# opaq_n2.net
KiCad netlist of a schematic drawn in EAGLE
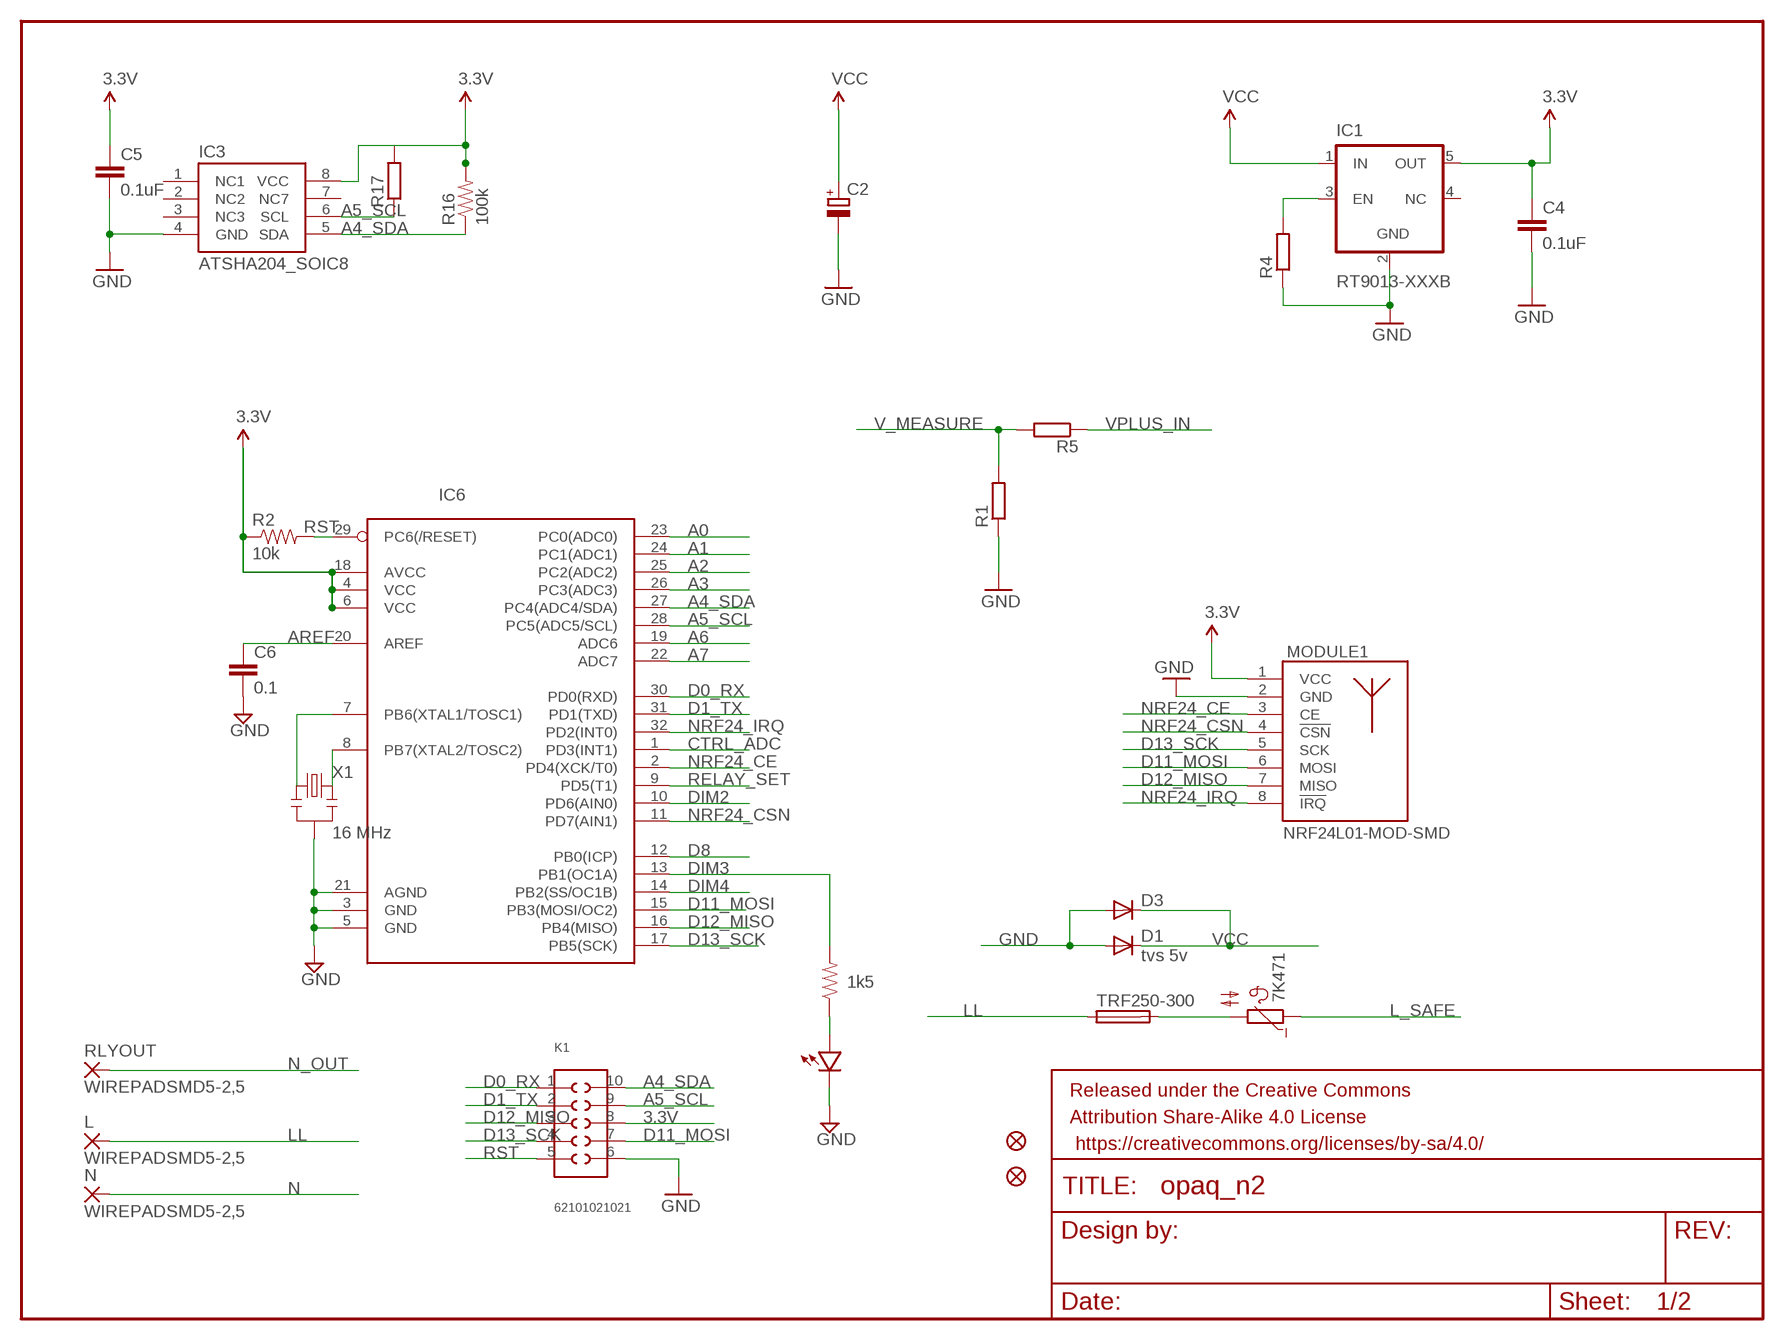
[diagram p0: schematic, sheet 1]
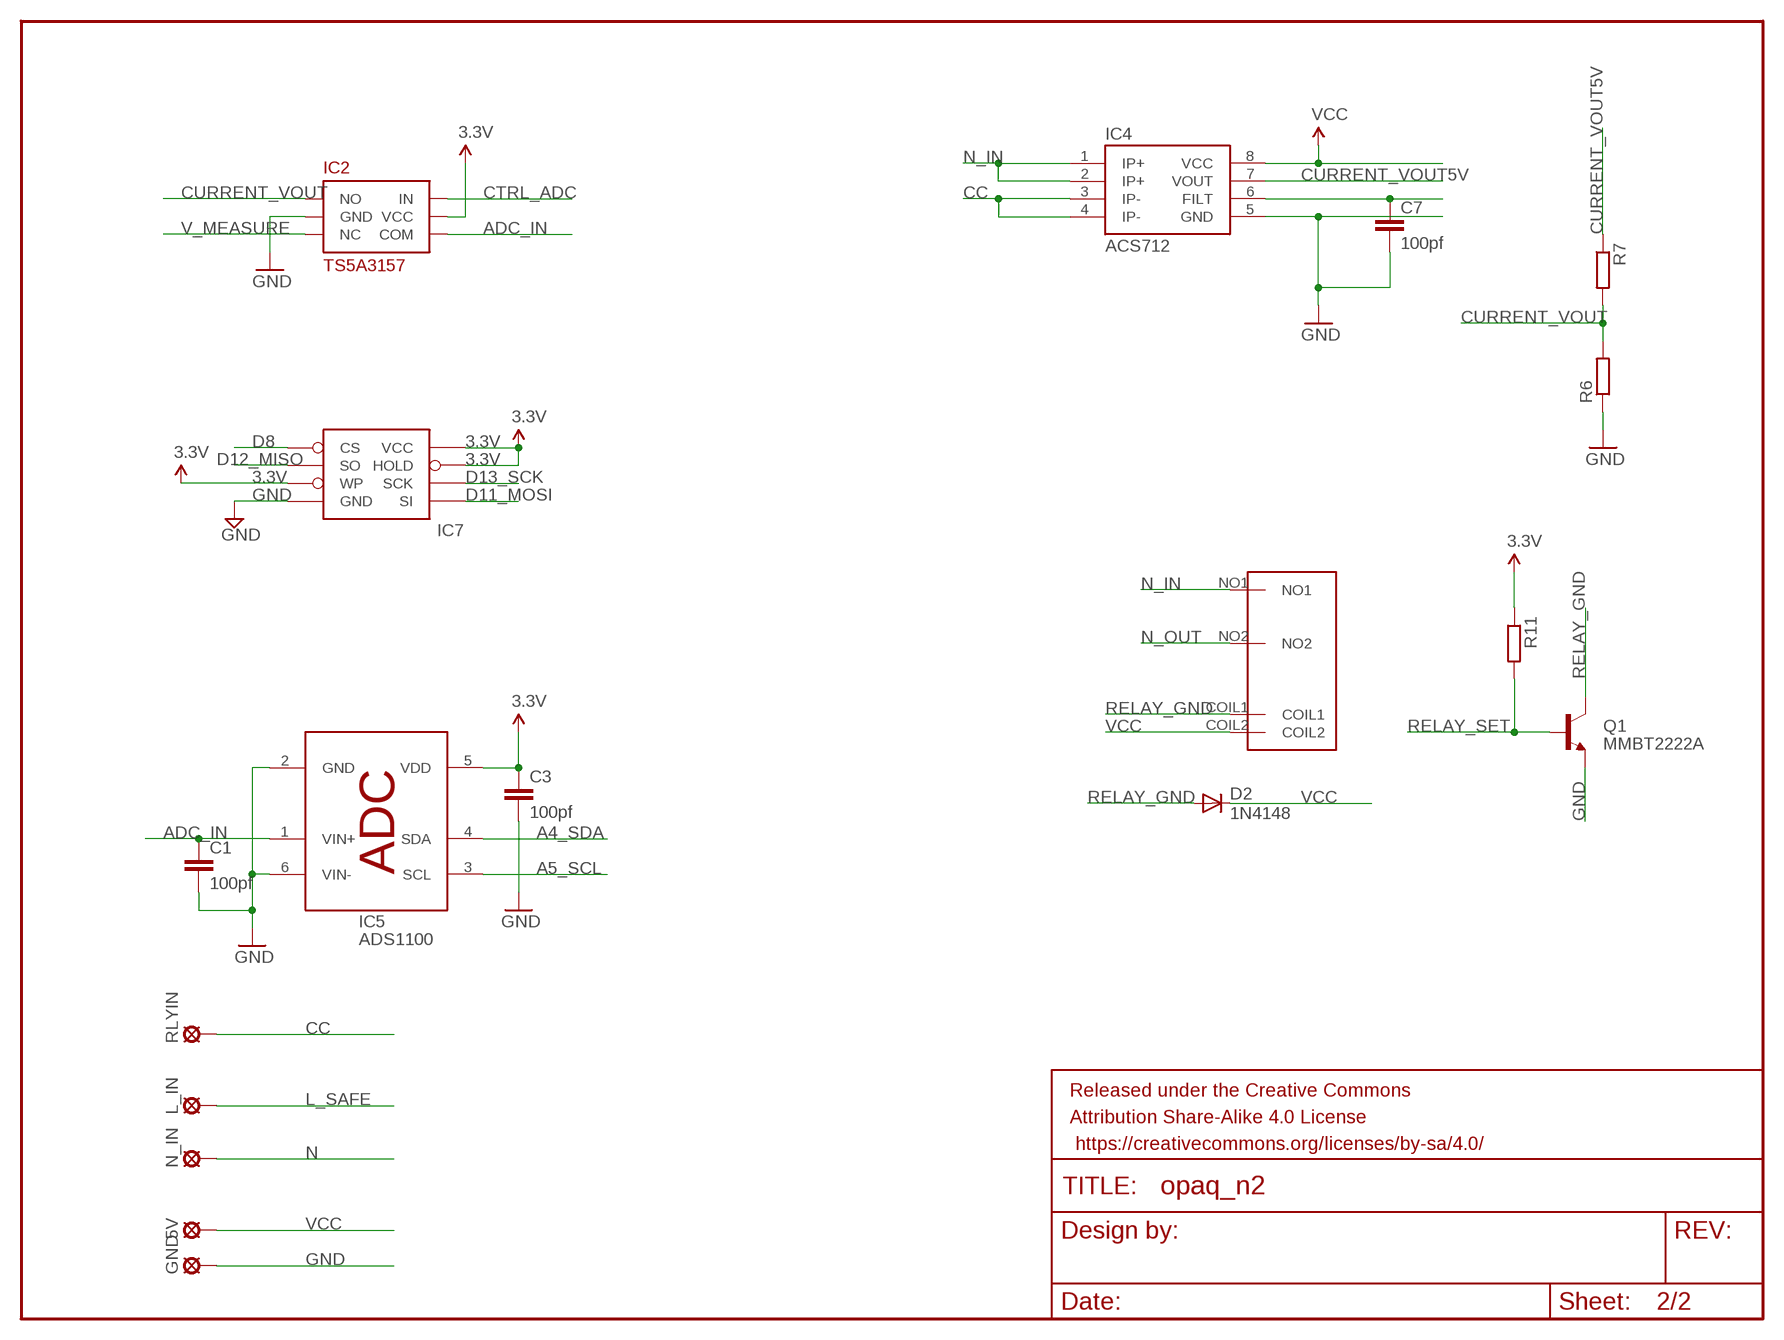
[diagram p1: schematic, sheet 2]

(export (version "E")
  (design (tool "Eeschema 10.0.6"))
  (components
    (comp (ref "7K471")
      (value "B57164")
      (footprint "eagle-import:B57164")
      (fields (field (name "MPN") "B57164K474K52"))
      (libsource (lib "eagle-import") (part "B57164"))
    )
    (comp (ref "C2")
      (value "CPOL-EUC/6032-28R")
      (footprint "eagle-import:C_6032-28R")
      (libsource (lib "eagle-import") (part "CPOL-EUC/6032-28R"))
    )
    (comp (ref "C4")
      (value "0.1uF")
      (footprint "eagle-import:0805")
      (libsource (lib "eagle-import") (part "SparkFun-Passives_CAP0805"))
    )
    (comp (ref "C5")
      (value "0.1uF")
      (footprint "eagle-import:0805")
      (libsource (lib "eagle-import") (part "SparkFun-Passives_CAP0805"))
    )
    (comp (ref "C6")
      (value "0.1")
      (footprint "eagle-import:0603-CAP")
      (libsource (lib "eagle-import") (part "CAP0603-CAP"))
    )
    (comp (ref "D1")
      (value "tvs 5v")
      (footprint "eagle-import:SOD-323")
      (libsource (lib "eagle-import") (part "DIODESOD"))
    )
    (comp (ref "D3")
      (value "DIODESMB")
      (footprint "eagle-import:SMB-DIODE")
      (libsource (lib "eagle-import") (part "DIODESMB"))
    )
    (comp (ref "DIM")
      (value "LED0603")
      (footprint "eagle-import:0603-LED")
      (libsource (lib "eagle-import") (part "LED0603"))
    )
    (comp (ref "FRAME1")
      (value "FRAME-LETTER")
      (footprint "eagle-import:CREATIVE_COMMONS")
      (libsource (lib "eagle-import") (part "FRAME-LETTER"))
    )
    (comp (ref "IC1")
      (value "RT9013-XXXB")
      (footprint "eagle-import:SOT23-5")
      (libsource (lib "eagle-import") (part "RT9013-XXXB"))
    )
    (comp (ref "IC3")
      (value "ATSHA204_SOIC8")
      (footprint "eagle-import:SOIC8")
      (libsource (lib "eagle-import") (part "ATSHA204_SOIC8"))
    )
    (comp (ref "IC6")
      (value "ATMega-328")
      (footprint "eagle-import:MLF32")
      (libsource (lib "eagle-import") (part "ATMEGA168/328MLF"))
    )
    (comp (ref "JP1")
      (value "FIDUCIAL1X2.5")
      (footprint "eagle-import:FIDUCIAL-1X2.5")
      (libsource (lib "eagle-import") (part "FIDUCIAL1X2.5"))
    )
    (comp (ref "JP2")
      (value "FIDUCIAL1X2.5")
      (footprint "eagle-import:FIDUCIAL-1X2.5")
      (libsource (lib "eagle-import") (part "FIDUCIAL1X2.5"))
    )
    (comp (ref "K1")
      (value "62101021021")
      (footprint "eagle-import:62101021021")
      (libsource (lib "eagle-import") (part "62101021021"))
    )
    (comp (ref "L")
      (value "WIREPADSMD5-2,5")
      (footprint "eagle-import:5-2,5")
      (libsource (lib "eagle-import") (part "WIREPADSMD5-2,5"))
    )
    (comp (ref "MODULE1")
      (value "NRF24L01-MOD-SMD")
      (footprint "eagle-import:SMD8-MODULE")
      (libsource (lib "eagle-import") (part "NRF24L01-MOD-SMD"))
    )
    (comp (ref "N")
      (value "WIREPADSMD5-2,5")
      (footprint "eagle-import:5-2,5")
      (libsource (lib "eagle-import") (part "WIREPADSMD5-2,5"))
    )
    (comp (ref "R1")
      (value "R-EU_R0805")
      (footprint "eagle-import:0805")
      (libsource (lib "eagle-import") (part "R-EU_R0805"))
    )
    (comp (ref "R2")
      (value "10k")
      (footprint "eagle-import:0603-RES")
      (libsource (lib "eagle-import") (part "RESISTOR0603-RES"))
    )
    (comp (ref "R3")
      (value "1k5")
      (footprint "eagle-import:0603-RES")
      (libsource (lib "eagle-import") (part "RESISTOR0603-RES"))
    )
    (comp (ref "R4")
      (value "R-EU_R0805")
      (footprint "eagle-import:0805")
      (libsource (lib "eagle-import") (part "R-EU_R0805"))
    )
    (comp (ref "R5")
      (value "R-EU_R0805")
      (footprint "eagle-import:0805")
      (libsource (lib "eagle-import") (part "R-EU_R0805"))
    )
    (comp (ref "R16")
      (value "100k")
      (footprint "eagle-import:0805")
      (libsource (lib "eagle-import") (part "SparkFun-Passives_RESISTOR0805-RES"))
    )
    (comp (ref "R17")
      (value "R-EU_R0805")
      (footprint "eagle-import:0805")
      (libsource (lib "eagle-import") (part "R-EU_R0805"))
    )
    (comp (ref "RLYOUT")
      (value "WIREPADSMD5-2,5")
      (footprint "eagle-import:5-2,5")
      (libsource (lib "eagle-import") (part "WIREPADSMD5-2,5"))
    )
    (comp (ref "TRF250-300")
      (value "TE5")
      (footprint "eagle-import:TE5")
      (libsource (lib "eagle-import") (part "TE5"))
    )
    (comp (ref "X1")
      (value "16 MHz")
      (footprint "eagle-import:RESONATOR-SMD")
      (libsource (lib "eagle-import") (part "RESONATORSMD"))
    )
    (comp (ref "5V")
      (value "MCS08")
      (footprint "eagle-import:MCS08")
      (libsource (lib "eagle-import") (part "MCS08"))
    )
    (comp (ref "C1")
      (value "100pf")
      (footprint "eagle-import:0402-CAP")
      (libsource (lib "eagle-import") (part "SparkFun-Passives_CAP0402-CAP"))
    )
    (comp (ref "C3")
      (value "100pf")
      (footprint "eagle-import:0402-CAP")
      (libsource (lib "eagle-import") (part "SparkFun-Passives_CAP0402-CAP"))
    )
    (comp (ref "C7")
      (value "100pf")
      (footprint "eagle-import:0402-CAP")
      (libsource (lib "eagle-import") (part "SparkFun-Passives_CAP0402-CAP"))
    )
    (comp (ref "D2")
      (value "1N4148")
      (footprint "eagle-import:SOD-323")
      (libsource (lib "eagle-import") (part "DIODESOD"))
    )
    (comp (ref "FRAME2")
      (value "FRAME-LETTERNO_PACKAGE")
      (footprint "eagle-import:DUMMY")
      (fields (field (name "DESIGNER") "Nobody"))
      (libsource (lib "eagle-import") (part "FRAME-LETTERNO_PACKAGE"))
    )
    (comp (ref "GND")
      (value "MCS08")
      (footprint "eagle-import:MCS08")
      (libsource (lib "eagle-import") (part "MCS08"))
    )
    (comp (ref "IC2")
      (value "TS5A3157")
      (footprint "eagle-import:SOT23-6")
      (libsource (lib "eagle-import") (part "TS5A3157"))
    )
    (comp (ref "IC4")
      (value "ACS712")
      (footprint "eagle-import:SO08")
      (libsource (lib "eagle-import") (part "ACS712"))
    )
    (comp (ref "IC5")
      (value "ADS1100")
      (footprint "eagle-import:SOT23-6")
      (fields (field (name "MF") "TI"))
      (libsource (lib "eagle-import") (part "ADS1100"))
    )
    (comp (ref "IC7")
      (value "AT25F512BWIDE_5.3MM")
      (footprint "eagle-import:SO08WIDE")
      (libsource (lib "eagle-import") (part "AT25F512BWIDE_5.3MM"))
    )
    (comp (ref "L_IN")
      (value "MCS08")
      (footprint "eagle-import:MCS08")
      (libsource (lib "eagle-import") (part "MCS08"))
    )
    (comp (ref "N_IN")
      (value "MCS08")
      (footprint "eagle-import:MCS08")
      (libsource (lib "eagle-import") (part "MCS08"))
    )
    (comp (ref "Q1")
      (value "MMBT2222A")
      (footprint "eagle-import:SOT23-3")
      (libsource (lib "eagle-import") (part "TRANSISTOR_NPNMMBT2222A"))
    )
    (comp (ref "R6")
      (value "R-EU_R0805")
      (footprint "eagle-import:0805")
      (libsource (lib "eagle-import") (part "R-EU_R0805"))
    )
    (comp (ref "R7")
      (value "R-EU_R0805")
      (footprint "eagle-import:0805")
      (libsource (lib "eagle-import") (part "R-EU_R0805"))
    )
    (comp (ref "R11")
      (value "R-EU_R0805")
      (footprint "eagle-import:0805")
      (libsource (lib "eagle-import") (part "R-EU_R0805"))
    )
    (comp (ref "RLYIN")
      (value "MCS08")
      (footprint "eagle-import:MCS08")
      (libsource (lib "eagle-import") (part "MCS08"))
    )
    (comp (ref "U$1")
      (value "OMRON_G6M-1A")
      (footprint "eagle-import:OMRON_G6M-1A")
      (libsource (lib "eagle-import") (part "OMRON_G6M-1A"))
    )
  )
  (nets
    (net (code "1") (name "3.3V") (class "Default")
      (node (ref "C3") (pin "1") (pinfunction "1_1") (pintype "passive"))
      (node (ref "C4") (pin "1") (pinfunction "1_1") (pintype "passive"))
      (node (ref "C5") (pin "1") (pinfunction "1_1") (pintype "passive"))
      (node (ref "IC1") (pin "5") (pinfunction "OUT_5") (pintype "passive"))
      (node (ref "IC2") (pin "5") (pinfunction "VCC_5") (pintype "bidirectional"))
      (node (ref "IC3") (pin "8") (pinfunction "VCC_8") (pintype "power_in"))
      (node (ref "IC5") (pin "5") (pinfunction "VDD_5") (pintype "power_in"))
      (node (ref "IC6") (pin "18") (pinfunction "AVCC_18") (pintype "bidirectional"))
      (node (ref "IC6") (pin "4") (pinfunction "VCC_4") (pintype "bidirectional"))
      (node (ref "IC6") (pin "6") (pinfunction "VCC_6") (pintype "bidirectional"))
      (node (ref "IC7") (pin "3") (pinfunction "WP_3") (pintype "bidirectional"))
      (node (ref "IC7") (pin "7") (pinfunction "HOLD_7") (pintype "bidirectional"))
      (node (ref "IC7") (pin "8") (pinfunction "VCC_8") (pintype "bidirectional"))
      (node (ref "K1") (pin "8") (pinfunction "8_8") (pintype "passive"))
      (node (ref "MODULE1") (pin "1") (pinfunction "VCC_1") (pintype "power_in"))
      (node (ref "R11") (pin "1") (pinfunction "1_1") (pintype "passive"))
      (node (ref "R16") (pin "2") (pinfunction "2_2") (pintype "passive"))
      (node (ref "R17") (pin "2") (pinfunction "2_2") (pintype "passive"))
      (node (ref "R2") (pin "1") (pinfunction "1_1") (pintype "passive"))
    )
    (net (code "2") (name "A0") (class "Default")
      (node (ref "IC6") (pin "23") (pinfunction "PC0(ADC0)_23") (pintype "bidirectional"))
    )
    (net (code "3") (name "A1") (class "Default")
      (node (ref "IC6") (pin "24") (pinfunction "PC1(ADC1)_24") (pintype "bidirectional"))
    )
    (net (code "4") (name "A2") (class "Default")
      (node (ref "IC6") (pin "25") (pinfunction "PC2(ADC2)_25") (pintype "bidirectional"))
    )
    (net (code "5") (name "A3") (class "Default")
      (node (ref "IC6") (pin "26") (pinfunction "PC3(ADC3)_26") (pintype "bidirectional"))
    )
    (net (code "6") (name "A4_SDA") (class "Default")
      (node (ref "IC3") (pin "5") (pinfunction "SDA_5") (pintype "bidirectional"))
      (node (ref "IC5") (pin "4") (pinfunction "SDA_4") (pintype "bidirectional"))
      (node (ref "IC6") (pin "27") (pinfunction "PC4(ADC4/SDA)_27") (pintype "bidirectional"))
      (node (ref "K1") (pin "10") (pinfunction "10_10") (pintype "passive"))
      (node (ref "R16") (pin "1") (pinfunction "1_1") (pintype "passive"))
    )
    (net (code "7") (name "A5_SCL") (class "Default")
      (node (ref "IC3") (pin "6") (pinfunction "SCL_6") (pintype "bidirectional"))
      (node (ref "IC5") (pin "3") (pinfunction "SCL_3") (pintype "input"))
      (node (ref "IC6") (pin "28") (pinfunction "PC5(ADC5/SCL)_28") (pintype "bidirectional"))
      (node (ref "K1") (pin "9") (pinfunction "9_9") (pintype "passive"))
      (node (ref "R17") (pin "1") (pinfunction "1_1") (pintype "passive"))
    )
    (net (code "8") (name "A6") (class "Default")
      (node (ref "IC6") (pin "19") (pinfunction "ADC6_19") (pintype "bidirectional"))
    )
    (net (code "9") (name "A7") (class "Default")
      (node (ref "IC6") (pin "22") (pinfunction "ADC7_22") (pintype "bidirectional"))
    )
    (net (code "10") (name "ADC_IN") (class "Default")
      (node (ref "C1") (pin "1") (pinfunction "1_1") (pintype "passive"))
      (node (ref "IC2") (pin "4") (pinfunction "COM_4") (pintype "bidirectional"))
      (node (ref "IC5") (pin "1") (pinfunction "VIN+_1") (pintype "input"))
    )
    (net (code "11") (name "AREF") (class "Default")
      (node (ref "C6") (pin "1") (pinfunction "1_1") (pintype "passive"))
      (node (ref "IC6") (pin "20") (pinfunction "AREF_20") (pintype "bidirectional"))
    )
    (net (code "12") (name "CC") (class "Default")
      (node (ref "IC4") (pin "3") (pinfunction "IP-_3") (pintype "bidirectional"))
      (node (ref "IC4") (pin "4") (pinfunction "IP-_4") (pintype "bidirectional"))
      (node (ref "RLYIN") (pin "MP") (pinfunction "MP_MP") (pintype "passive"))
    )
    (net (code "13") (name "CTRL_ADC") (class "Default")
      (node (ref "IC2") (pin "6") (pinfunction "IN_6") (pintype "bidirectional"))
      (node (ref "IC6") (pin "1") (pinfunction "PD3(INT1)_1") (pintype "bidirectional"))
    )
    (net (code "14") (name "CURRENT_VOUT") (class "Default")
      (node (ref "IC2") (pin "1") (pinfunction "NO_1") (pintype "bidirectional"))
      (node (ref "R6") (pin "2") (pinfunction "2_2") (pintype "passive"))
      (node (ref "R7") (pin "2") (pinfunction "2_2") (pintype "passive"))
    )
    (net (code "15") (name "CURRENT_VOUT5V") (class "Default")
      (node (ref "IC4") (pin "7") (pinfunction "VOUT_7") (pintype "bidirectional"))
      (node (ref "R7") (pin "1") (pinfunction "1_1") (pintype "passive"))
    )
    (net (code "16") (name "D0_RX") (class "Default")
      (node (ref "IC6") (pin "30") (pinfunction "PD0(RXD)_30") (pintype "bidirectional"))
      (node (ref "K1") (pin "1") (pinfunction "1_1") (pintype "passive"))
    )
    (net (code "17") (name "D1_TX") (class "Default")
      (node (ref "IC6") (pin "31") (pinfunction "PD1(TXD)_31") (pintype "bidirectional"))
      (node (ref "K1") (pin "2") (pinfunction "2_2") (pintype "passive"))
    )
    (net (code "18") (name "D8") (class "Default")
      (node (ref "IC6") (pin "12") (pinfunction "PB0(ICP)_12") (pintype "bidirectional"))
      (node (ref "IC7") (pin "1") (pinfunction "CS_1") (pintype "bidirectional"))
    )
    (net (code "19") (name "D11_MOSI") (class "Default")
      (node (ref "IC6") (pin "15") (pinfunction "PB3(MOSI/OC2)_15") (pintype "bidirectional"))
      (node (ref "IC7") (pin "5") (pinfunction "SI_5") (pintype "bidirectional"))
      (node (ref "K1") (pin "7") (pinfunction "7_7") (pintype "passive"))
      (node (ref "MODULE1") (pin "6") (pinfunction "MOSI_6") (pintype "input"))
    )
    (net (code "20") (name "D12_MISO") (class "Default")
      (node (ref "IC6") (pin "16") (pinfunction "PB4(MISO)_16") (pintype "bidirectional"))
      (node (ref "IC7") (pin "2") (pinfunction "SO_2") (pintype "bidirectional"))
      (node (ref "K1") (pin "3") (pinfunction "3_3") (pintype "passive"))
      (node (ref "MODULE1") (pin "7") (pinfunction "MISO_7") (pintype "output"))
    )
    (net (code "21") (name "D13_SCK") (class "Default")
      (node (ref "IC6") (pin "17") (pinfunction "PB5(SCK)_17") (pintype "bidirectional"))
      (node (ref "IC7") (pin "6") (pinfunction "SCK_6") (pintype "bidirectional"))
      (node (ref "K1") (pin "4") (pinfunction "4_4") (pintype "passive"))
      (node (ref "MODULE1") (pin "5") (pinfunction "SCK_5") (pintype "input"))
    )
    (net (code "22") (name "DIM2") (class "Default")
      (node (ref "IC6") (pin "10") (pinfunction "PD6(AIN0)_10") (pintype "bidirectional"))
    )
    (net (code "23") (name "DIM3") (class "Default")
      (node (ref "IC6") (pin "13") (pinfunction "PB1(OC1A)_13") (pintype "bidirectional"))
      (node (ref "R3") (pin "2") (pinfunction "2_2") (pintype "passive"))
    )
    (net (code "24") (name "DIM4") (class "Default")
      (node (ref "IC6") (pin "14") (pinfunction "PB2(SS/OC1B)_14") (pintype "bidirectional"))
    )
    (net (code "25") (name "GND") (class "Default")
      (node (ref "C1") (pin "2") (pinfunction "2_2") (pintype "passive"))
      (node (ref "C2") (pin "-") (pinfunction "-_-") (pintype "passive"))
      (node (ref "C3") (pin "2") (pinfunction "2_2") (pintype "passive"))
      (node (ref "C4") (pin "2") (pinfunction "2_2") (pintype "passive"))
      (node (ref "C5") (pin "2") (pinfunction "2_2") (pintype "passive"))
      (node (ref "C6") (pin "2") (pinfunction "2_2") (pintype "passive"))
      (node (ref "C7") (pin "2") (pinfunction "2_2") (pintype "passive"))
      (node (ref "D1") (pin "2") (pinfunction "A_2") (pintype "passive"))
      (node (ref "D3") (pin "A") (pinfunction "A_A") (pintype "passive"))
      (node (ref "DIM") (pin "MINUS") (pinfunction "MINUS_MINUS") (pintype "passive"))
      (node (ref "GND") (pin "MP") (pinfunction "MP_MP") (pintype "passive"))
      (node (ref "IC1") (pin "2") (pinfunction "GND_2") (pintype "power_in"))
      (node (ref "IC2") (pin "2") (pinfunction "GND_2") (pintype "bidirectional"))
      (node (ref "IC3") (pin "4") (pinfunction "GND_4") (pintype "power_in"))
      (node (ref "IC4") (pin "5") (pinfunction "GND_5") (pintype "bidirectional"))
      (node (ref "IC5") (pin "2") (pinfunction "GND_2") (pintype "power_in"))
      (node (ref "IC5") (pin "6") (pinfunction "VIN-_6") (pintype "input"))
      (node (ref "IC6") (pin "21") (pinfunction "AGND_21") (pintype "bidirectional"))
      (node (ref "IC6") (pin "3") (pinfunction "GND_3") (pintype "bidirectional"))
      (node (ref "IC6") (pin "5") (pinfunction "GND_5") (pintype "bidirectional"))
      (node (ref "IC7") (pin "4") (pinfunction "GND_4") (pintype "bidirectional"))
      (node (ref "K1") (pin "6") (pinfunction "6_6") (pintype "passive"))
      (node (ref "MODULE1") (pin "2") (pinfunction "GND_2") (pintype "power_in"))
      (node (ref "Q1") (pin "2") (pinfunction "E_2") (pintype "passive"))
      (node (ref "R1") (pin "1") (pinfunction "1_1") (pintype "passive"))
      (node (ref "R4") (pin "1") (pinfunction "1_1") (pintype "passive"))
      (node (ref "R6") (pin "1") (pinfunction "1_1") (pintype "passive"))
      (node (ref "X1") (pin "2") (pinfunction "2_2") (pintype "passive"))
    )
    (net (code "26") (name "LL") (class "Default")
      (node (ref "L") (pin "1") (pinfunction "P_1") (pintype "passive"))
      (node (ref "TRF250-300") (pin "1") (pinfunction "1_1") (pintype "passive"))
    )
    (net (code "27") (name "L_SAFE") (class "Default")
      (node (ref "7K471") (pin "1") (pinfunction "1_1") (pintype "passive"))
      (node (ref "L_IN") (pin "MP") (pinfunction "MP_MP") (pintype "passive"))
    )
    (net (code "28") (name "N") (class "Default")
      (node (ref "N") (pin "1") (pinfunction "P_1") (pintype "passive"))
      (node (ref "N_IN") (pin "MP") (pinfunction "MP_MP") (pintype "passive"))
    )
    (net (code "29") (name "NRF24_CE") (class "Default")
      (node (ref "IC6") (pin "2") (pinfunction "PD4(XCK/T0)_2") (pintype "bidirectional"))
      (node (ref "MODULE1") (pin "3") (pinfunction "CE_3") (pintype "input"))
    )
    (net (code "30") (name "NRF24_CSN") (class "Default")
      (node (ref "IC6") (pin "11") (pinfunction "PD7(AIN1)_11") (pintype "bidirectional"))
      (node (ref "MODULE1") (pin "4") (pinfunction "~{CSN}_4") (pintype "input"))
    )
    (net (code "31") (name "NRF24_IRQ") (class "Default")
      (node (ref "IC6") (pin "32") (pinfunction "PD2(INT0)_32") (pintype "bidirectional"))
      (node (ref "MODULE1") (pin "8") (pinfunction "~{IRQ}_8") (pintype "open_collector"))
    )
    (net (code "32") (name "N_IN") (class "Default")
      (node (ref "IC4") (pin "1") (pinfunction "IP+_1") (pintype "bidirectional"))
      (node (ref "IC4") (pin "2") (pinfunction "IP+_2") (pintype "bidirectional"))
      (node (ref "U$1") (pin "NO1") (pinfunction "NO1_NO1") (pintype "bidirectional"))
    )
    (net (code "33") (name "N_OUT") (class "Default")
      (node (ref "RLYOUT") (pin "1") (pinfunction "P_1") (pintype "passive"))
      (node (ref "U$1") (pin "NO2") (pinfunction "NO2_NO2") (pintype "bidirectional"))
    )
    (net (code "34") (name "Net-(7K471-Pad2)") (class "Default")
      (node (ref "7K471") (pin "2") (pinfunction "2_2") (pintype "passive"))
      (node (ref "TRF250-300") (pin "2") (pinfunction "2_2") (pintype "passive"))
    )
    (net (code "35") (name "Net-(DIM-PadPLUS)") (class "Default")
      (node (ref "DIM") (pin "PLUS") (pinfunction "PLUS_PLUS") (pintype "passive"))
      (node (ref "R3") (pin "1") (pinfunction "1_1") (pintype "passive"))
    )
    (net (code "36") (name "Net-(IC1-EN)") (class "Default")
      (node (ref "IC1") (pin "3") (pinfunction "EN_3") (pintype "input"))
      (node (ref "R4") (pin "2") (pinfunction "2_2") (pintype "passive"))
    )
    (net (code "37") (name "Net-(IC4-FILT)") (class "Default")
      (node (ref "C7") (pin "1") (pinfunction "1_1") (pintype "passive"))
      (node (ref "IC4") (pin "6") (pinfunction "FILT_6") (pintype "bidirectional"))
    )
    (net (code "38") (name "Net-(IC6-PB6(XTAL1{slash}TOSC1))") (class "Default")
      (node (ref "IC6") (pin "7") (pinfunction "PB6(XTAL1/TOSC1)_7") (pintype "bidirectional"))
      (node (ref "X1") (pin "1") (pinfunction "1_1") (pintype "passive"))
    )
    (net (code "39") (name "Net-(IC6-PB7(XTAL2{slash}TOSC2))") (class "Default")
      (node (ref "IC6") (pin "8") (pinfunction "PB7(XTAL2/TOSC2)_8") (pintype "bidirectional"))
      (node (ref "X1") (pin "3") (pinfunction "3_3") (pintype "passive"))
    )
    (net (code "40") (name "RELAY_GND") (class "Default")
      (node (ref "D2") (pin "2") (pinfunction "A_2") (pintype "passive"))
      (node (ref "Q1") (pin "3") (pinfunction "C_3") (pintype "passive"))
      (node (ref "U$1") (pin "COIL1") (pinfunction "COIL1_COIL1") (pintype "bidirectional"))
    )
    (net (code "41") (name "RELAY_SET") (class "Default")
      (node (ref "IC6") (pin "9") (pinfunction "PD5(T1)_9") (pintype "bidirectional"))
      (node (ref "Q1") (pin "1") (pinfunction "B_1") (pintype "passive"))
      (node (ref "R11") (pin "2") (pinfunction "2_2") (pintype "passive"))
    )
    (net (code "42") (name "RST") (class "Default")
      (node (ref "IC6") (pin "29") (pinfunction "PC6(/RESET)_29") (pintype "bidirectional"))
      (node (ref "K1") (pin "5") (pinfunction "5_5") (pintype "passive"))
      (node (ref "R2") (pin "2") (pinfunction "2_2") (pintype "passive"))
    )
    (net (code "43") (name "VCC") (class "Default")
      (node (ref "5V") (pin "MP") (pinfunction "MP_MP") (pintype "passive"))
      (node (ref "C2") (pin "+") (pinfunction "+_+") (pintype "passive"))
      (node (ref "D1") (pin "1") (pinfunction "C_1") (pintype "passive"))
      (node (ref "D2") (pin "1") (pinfunction "C_1") (pintype "passive"))
      (node (ref "D3") (pin "C") (pinfunction "C_C") (pintype "passive"))
      (node (ref "IC1") (pin "1") (pinfunction "IN_1") (pintype "input"))
      (node (ref "IC4") (pin "8") (pinfunction "VCC_8") (pintype "bidirectional"))
      (node (ref "U$1") (pin "COIL2") (pinfunction "COIL2_COIL2") (pintype "bidirectional"))
    )
    (net (code "44") (name "VPLUS_IN") (class "Default")
      (node (ref "R5") (pin "1") (pinfunction "1_1") (pintype "passive"))
    )
    (net (code "45") (name "V_MEASURE") (class "Default")
      (node (ref "IC2") (pin "3") (pinfunction "NC_3") (pintype "bidirectional"))
      (node (ref "R1") (pin "2") (pinfunction "2_2") (pintype "passive"))
      (node (ref "R5") (pin "2") (pinfunction "2_2") (pintype "passive"))
    )
    (net (code "46") (name "unconnected-(IC1-NC-Pad4)") (class "Default")
      (node (ref "IC1") (pin "4") (pinfunction "NC_4") (pintype "no_connect"))
    )
    (net (code "47") (name "unconnected-(IC3-NC1-Pad1)") (class "Default")
      (node (ref "IC3") (pin "1") (pinfunction "NC1_1") (pintype "no_connect"))
    )
    (net (code "48") (name "unconnected-(IC3-NC2-Pad2)") (class "Default")
      (node (ref "IC3") (pin "2") (pinfunction "NC2_2") (pintype "no_connect"))
    )
    (net (code "49") (name "unconnected-(IC3-NC3-Pad3)") (class "Default")
      (node (ref "IC3") (pin "3") (pinfunction "NC3_3") (pintype "no_connect"))
    )
    (net (code "50") (name "unconnected-(IC3-NC7-Pad7)") (class "Default")
      (node (ref "IC3") (pin "7") (pinfunction "NC7_7") (pintype "no_connect"))
    )
  )
)
